# EncAMT203_Cat6_180223.net
KiCad netlist of a schematic drawn in EAGLE
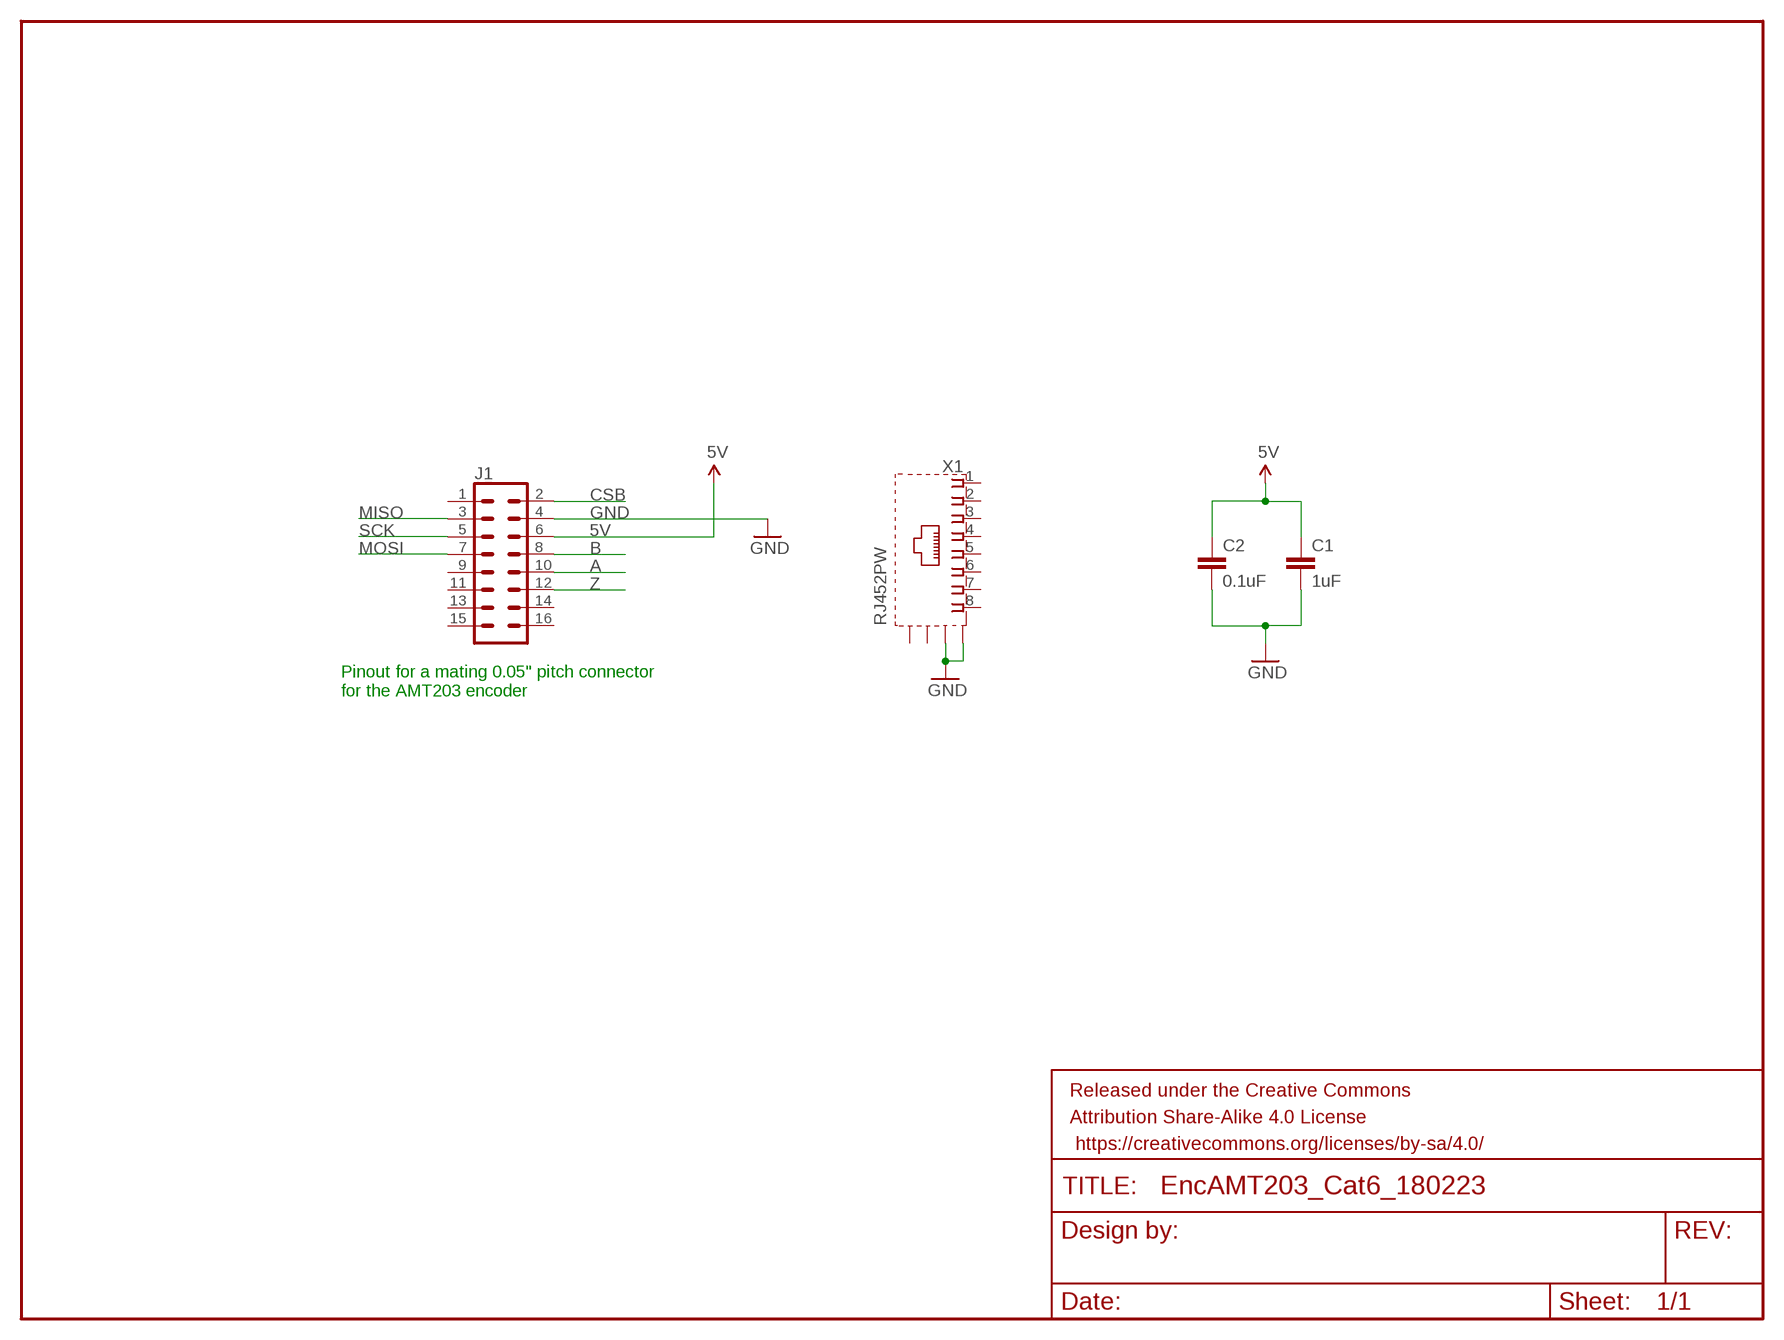
[diagram p0: schematic, sheet 1]

(export (version "E")
  (design (tool "Eeschema 10.0.6"))
  (components
    (comp (ref "C1")
      (value "1uF")
      (footprint "eagle-import:0603")
      (libsource (lib "eagle-import") (part "0.1UF-0603-25V-5%"))
    )
    (comp (ref "C2")
      (value "0.1uF")
      (footprint "eagle-import:0603")
      (libsource (lib "eagle-import") (part "0.1UF-0603-25V-5%"))
    )
    (comp (ref "FRAME1")
      (value "FRAME-LETTERNO_PACKAGE")
      (footprint "eagle-import:DUMMY")
      (fields (field (name "DESIGNER") "Nobody"))
      (libsource (lib "eagle-import") (part "FRAME-LETTERNO_PACKAGE"))
    )
    (comp (ref "J1")
      (value "CONN_08X2_1.27MM")
      (footprint "eagle-import:2X08_1.27MM")
      (libsource (lib "eagle-import") (part "CONN_08X2_1.27MM"))
    )
    (comp (ref "X1")
      (value "RJ452PW")
      (footprint "eagle-import:RJ45-SHIELD1")
      (libsource (lib "eagle-import") (part "RJ452PW"))
    )
  )
  (nets
    (net (code "1") (name "/A") (class "Default")
      (node (ref "J1") (pin "10") (pinfunction "10_10") (pintype "passive"))
    )
    (net (code "2") (name "/B") (class "Default")
      (node (ref "J1") (pin "8") (pinfunction "8_8") (pintype "passive"))
    )
    (net (code "3") (name "/CSB") (class "Default")
      (node (ref "J1") (pin "2") (pinfunction "2_2") (pintype "passive"))
    )
    (net (code "4") (name "/MISO") (class "Default")
      (node (ref "J1") (pin "3") (pinfunction "3_3") (pintype "passive"))
    )
    (net (code "5") (name "/MOSI") (class "Default")
      (node (ref "J1") (pin "7") (pinfunction "7_7") (pintype "passive"))
    )
    (net (code "6") (name "/SCK") (class "Default")
      (node (ref "J1") (pin "5") (pinfunction "5_5") (pintype "passive"))
    )
    (net (code "7") (name "/Z") (class "Default")
      (node (ref "J1") (pin "12") (pinfunction "12_12") (pintype "passive"))
    )
    (net (code "8") (name "5V") (class "Default")
      (node (ref "C1") (pin "1") (pinfunction "1_1") (pintype "passive"))
      (node (ref "C2") (pin "1") (pinfunction "1_1") (pintype "passive"))
      (node (ref "J1") (pin "6") (pinfunction "6_6") (pintype "passive"))
    )
    (net (code "9") (name "GND") (class "Default")
      (node (ref "C1") (pin "2") (pinfunction "2_2") (pintype "passive"))
      (node (ref "C2") (pin "2") (pinfunction "2_2") (pintype "passive"))
      (node (ref "J1") (pin "4") (pinfunction "4_4") (pintype "passive"))
      (node (ref "X1") (pin "S1") (pinfunction "S_S1") (pintype "passive"))
      (node (ref "X1") (pin "S2") (pinfunction "S_S2") (pintype "passive"))
    )
    (net (code "10") (name "unconnected-(J1-Pad1)") (class "Default")
      (node (ref "J1") (pin "1") (pinfunction "1_1") (pintype "passive"))
    )
    (net (code "11") (name "unconnected-(J1-Pad9)") (class "Default")
      (node (ref "J1") (pin "9") (pinfunction "9_9") (pintype "passive"))
    )
    (net (code "12") (name "unconnected-(J1-Pad11)") (class "Default")
      (node (ref "J1") (pin "11") (pinfunction "11_11") (pintype "passive"))
    )
    (net (code "13") (name "unconnected-(J1-Pad13)") (class "Default")
      (node (ref "J1") (pin "13") (pinfunction "13_13") (pintype "passive"))
    )
    (net (code "14") (name "unconnected-(J1-Pad14)") (class "Default")
      (node (ref "J1") (pin "14") (pinfunction "14_14") (pintype "passive"))
    )
    (net (code "15") (name "unconnected-(J1-Pad15)") (class "Default")
      (node (ref "J1") (pin "15") (pinfunction "15_15") (pintype "passive"))
    )
    (net (code "16") (name "unconnected-(J1-Pad16)") (class "Default")
      (node (ref "J1") (pin "16") (pinfunction "16_16") (pintype "passive"))
    )
    (net (code "17") (name "unconnected-(X1-Pad1)") (class "Default")
      (node (ref "X1") (pin "1") (pinfunction "1_1") (pintype "passive"))
    )
    (net (code "18") (name "unconnected-(X1-Pad2)") (class "Default")
      (node (ref "X1") (pin "2") (pinfunction "2_2") (pintype "passive"))
    )
    (net (code "19") (name "unconnected-(X1-Pad3)") (class "Default")
      (node (ref "X1") (pin "3") (pinfunction "3_3") (pintype "passive"))
    )
    (net (code "20") (name "unconnected-(X1-Pad4)") (class "Default")
      (node (ref "X1") (pin "4") (pinfunction "4_4") (pintype "passive"))
    )
    (net (code "21") (name "unconnected-(X1-Pad5)") (class "Default")
      (node (ref "X1") (pin "5") (pinfunction "5_5") (pintype "passive"))
    )
    (net (code "22") (name "unconnected-(X1-Pad6)") (class "Default")
      (node (ref "X1") (pin "6") (pinfunction "6_6") (pintype "passive"))
    )
    (net (code "23") (name "unconnected-(X1-Pad7)") (class "Default")
      (node (ref "X1") (pin "7") (pinfunction "7_7") (pintype "passive"))
    )
    (net (code "24") (name "unconnected-(X1-Pad8)") (class "Default")
      (node (ref "X1") (pin "8") (pinfunction "8_8") (pintype "passive"))
    )
    (net (code "25") (name "unconnected-(X1-S-PadS3)") (class "Default")
      (node (ref "X1") (pin "S3") (pinfunction "S_S3") (pintype "passive"))
    )
    (net (code "26") (name "unconnected-(X1-S-PadS4)") (class "Default")
      (node (ref "X1") (pin "S4") (pinfunction "S_S4") (pintype "passive"))
    )
  )
)
